# Main.net
KiCad netlist of a schematic drawn in Altium Designer
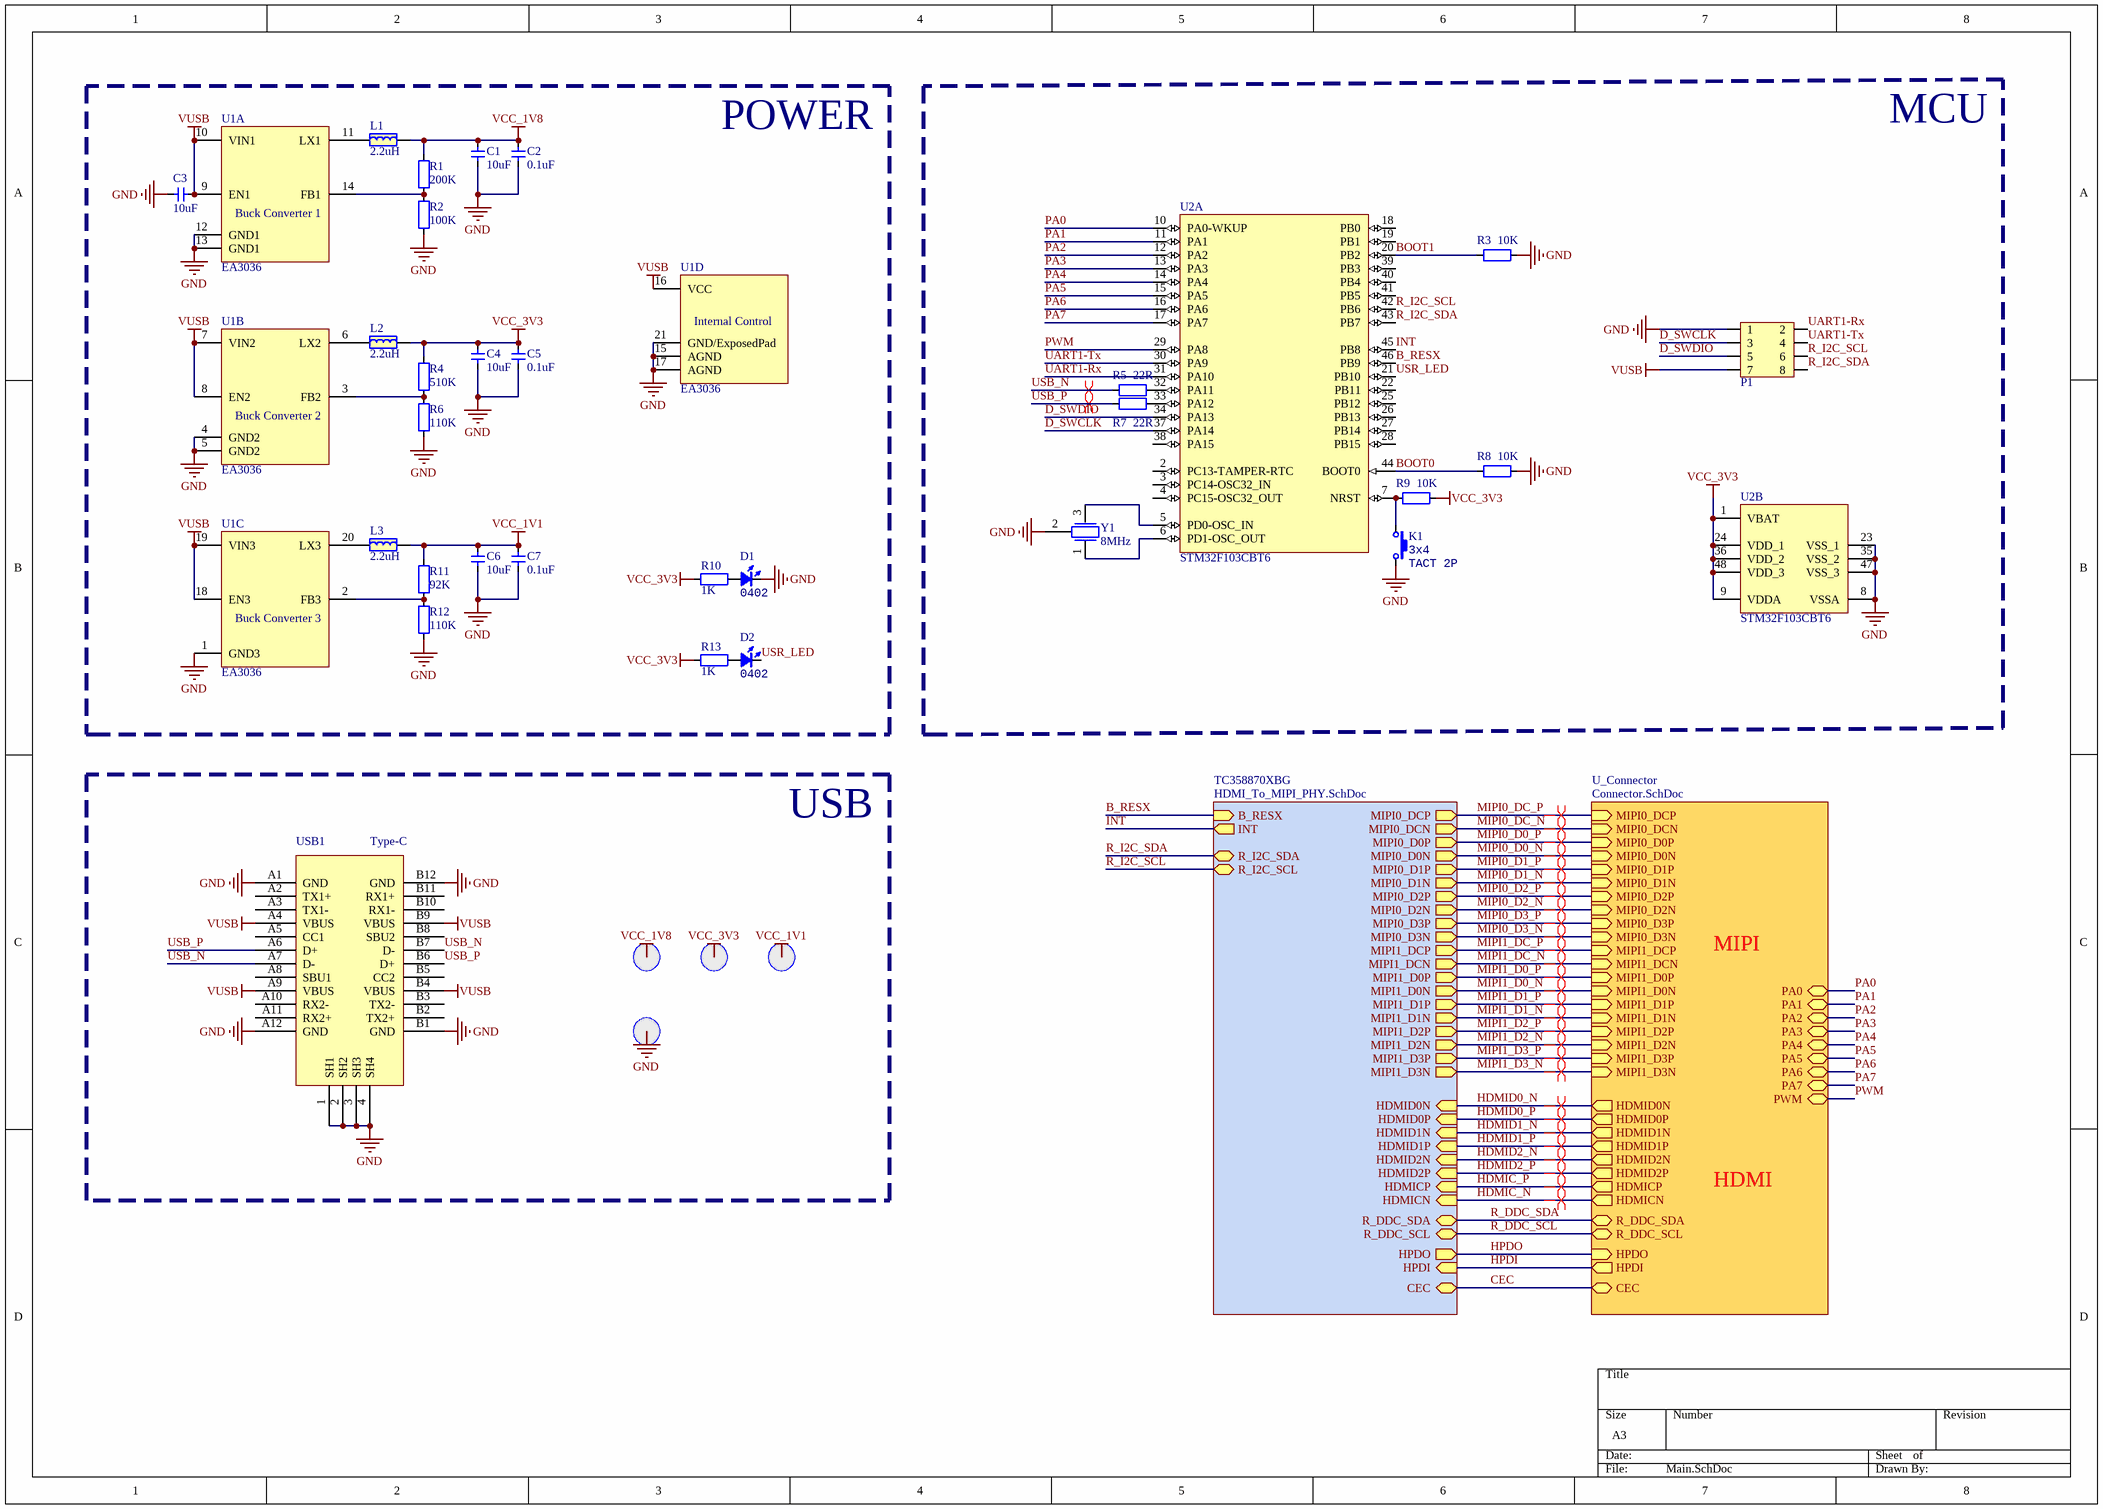
[diagram p0: Main.SchDoc]

(export (version "E")
  (design (tool "Eeschema 10.0.6"))
  (components
    (comp (ref "C1")
      (value "10uF")
      (footprint "CAP_0402")
      (description "Capacitor")
      (libsource (lib "MyPcbLib") (part "电容-0402"))
    )
    (comp (ref "C2")
      (value "0.1uF")
      (footprint "CAP_0402")
      (description "Capacitor")
      (libsource (lib "MyPcbLib") (part "电容-0402"))
    )
    (comp (ref "C3")
      (value "10uF")
      (footprint "CAP_0402")
      (description "Capacitor")
      (libsource (lib "MyPcbLib") (part "电容-0402"))
    )
    (comp (ref "C4")
      (value "10uF")
      (footprint "CAP_0402")
      (description "Capacitor")
      (libsource (lib "MyPcbLib") (part "电容-0402"))
    )
    (comp (ref "C5")
      (value "0.1uF")
      (footprint "CAP_0402")
      (description "Capacitor")
      (libsource (lib "MyPcbLib") (part "电容-0402"))
    )
    (comp (ref "C6")
      (value "10uF")
      (footprint "CAP_0402")
      (description "Capacitor")
      (libsource (lib "MyPcbLib") (part "电容-0402"))
    )
    (comp (ref "C7")
      (value "0.1uF")
      (footprint "CAP_0402")
      (description "Capacitor")
      (libsource (lib "MyPcbLib") (part "电容-0402"))
    )
    (comp (ref "D1")
      (value "color?")
      (footprint "LED_0402_RED")
      (description "LED")
      (fields (field (name "TYPE") "0402"))
      (libsource (lib "KitSprout") (part "LED_0402"))
    )
    (comp (ref "D2")
      (value "color?")
      (footprint "LED_0402_RED")
      (description "LED")
      (fields (field (name "TYPE") "0402"))
      (libsource (lib "KitSprout") (part "LED_0402"))
    )
    (comp (ref "K1")
      (value "3x4")
      (footprint "ButtonTACT_3x4x2_180H")
      (description "Button")
      (fields (field (name "TYPE") "TACT 2P") (field (name "Comment") "TACT 2P"))
      (libsource (lib "KitSprout") (part "ButtonTACT_3x4x2_180"))
    )
    (comp (ref "L1")
      (value "2.2uH")
      (footprint "2520-L")
      (description "磁珠")
      (libsource (lib "MyPcbLib") (part "电感-2520"))
    )
    (comp (ref "L2")
      (value "2.2uH")
      (footprint "2520-L")
      (description "磁珠")
      (libsource (lib "MyPcbLib") (part "电感-2520"))
    )
    (comp (ref "L3")
      (value "2.2uH")
      (footprint "2520-L")
      (description "磁珠")
      (libsource (lib "MyPcbLib") (part "电感-2520"))
    )
    (comp (ref "P1")
      (value "HDR2x4_2.54")
      (footprint "HDR2X4_2.54_180H")
      (description "Header")
      (libsource (lib "MyPcbLib") (part "HDR2x4_2.54"))
    )
    (comp (ref "R1")
      (value "200K")
      (footprint "RES_0402")
      (description "Resistor")
      (libsource (lib "MyPcbLib") (part "电阻-0402"))
    )
    (comp (ref "R2")
      (value "100K")
      (footprint "RES_0402")
      (description "Resistor")
      (libsource (lib "MyPcbLib") (part "电阻-0402"))
    )
    (comp (ref "R3")
      (value "10K")
      (footprint "RES_0402")
      (description "Resistor")
      (libsource (lib "") (part "电阻-0402_1"))
    )
    (comp (ref "R4")
      (value "510K")
      (footprint "RES_0402")
      (description "Resistor")
      (libsource (lib "MyPcbLib") (part "电阻-0402"))
    )
    (comp (ref "R5")
      (value "22R")
      (footprint "RES_0402")
      (description "Resistor")
      (libsource (lib "") (part "电阻-0402_1"))
    )
    (comp (ref "R6")
      (value "110K")
      (footprint "RES_0402")
      (description "Resistor")
      (libsource (lib "MyPcbLib") (part "电阻-0402"))
    )
    (comp (ref "R7")
      (value "22R")
      (footprint "RES_0402")
      (description "Resistor")
      (libsource (lib "") (part "电阻-0402_1"))
    )
    (comp (ref "R8")
      (value "10K")
      (footprint "RES_0402")
      (description "Resistor")
      (libsource (lib "") (part "电阻-0402_1"))
    )
    (comp (ref "R9")
      (value "10K")
      (footprint "RES_0402")
      (description "Resistor")
      (libsource (lib "") (part "电阻-0402_1"))
    )
    (comp (ref "R10")
      (value "1K")
      (footprint "RES_0402")
      (description "Resistor")
      (libsource (lib "") (part "电阻-0402_1"))
    )
    (comp (ref "R11")
      (value "92K")
      (footprint "RES_0402")
      (description "Resistor")
      (libsource (lib "MyPcbLib") (part "电阻-0402"))
    )
    (comp (ref "R12")
      (value "110K")
      (footprint "RES_0402")
      (description "Resistor")
      (libsource (lib "MyPcbLib") (part "电阻-0402"))
    )
    (comp (ref "R13")
      (value "1K")
      (footprint "RES_0402")
      (description "Resistor")
      (libsource (lib "") (part "电阻-0402_1"))
    )
    (comp (ref "T1") (value "测试点") (footprint "TEST_PT") (libsource (lib "MyPcbLib") (part "测试点")))
    (comp (ref "T2") (value "测试点") (footprint "TEST_PT") (libsource (lib "MyPcbLib") (part "测试点")))
    (comp (ref "T3") (value "测试点") (footprint "TEST_PT") (libsource (lib "MyPcbLib") (part "测试点")))
    (comp (ref "T4") (value "测试点") (footprint "TEST_PT") (libsource (lib "MyPcbLib") (part "测试点")))
    (comp (ref "U1") (value "EA3036") (footprint "QFN-20") (libsource (lib "mLib") (part "EA3036")))
    (comp (ref "U2")
      (value "STM32F103CBT6")
      (footprint "LQFP-48")
      (libsource (lib "STMicroelectronics STM32 F1") (part "STM32F103CBT6"))
    )
    (comp (ref "USB1")
      (value "Type-C")
      (footprint "Type-C-TOP")
      (libsource (lib "MyPcbLib") (part "USB-Type-C-TOP"))
    )
    (comp (ref "Y1")
      (value "8MHz")
      (footprint "晶振-3P")
      (description "村田贴片")
      (libsource (lib "MyPcbLib") (part "晶振-3Pin"))
    )
  )
  (nets
    (net (code "1") (name "/BOOT0") (class "Default")
      (node (ref "R8") (pin "1") (pinfunction "1_1") (pintype "passive"))
      (node (ref "U2") (pin "44") (pinfunction "BOOT0_44") (pintype "input"))
    )
    (net (code "2") (name "/BOOT1") (class "Default")
      (node (ref "R3") (pin "1") (pinfunction "1_1") (pintype "passive"))
      (node (ref "U2") (pin "20") (pinfunction "PB2_20") (pintype "bidirectional"))
    )
    (net (code "3") (name "/B_RESX") (class "Default")
      (node (ref "U2") (pin "46") (pinfunction "PB9_46") (pintype "bidirectional"))
    )
    (net (code "5") (name "/D_SWCLK") (class "Default")
      (node (ref "P1") (pin "3") (pinfunction "3_3") (pintype "passive"))
      (node (ref "U2") (pin "37") (pinfunction "PA14_37") (pintype "bidirectional"))
    )
    (net (code "6") (name "/D_SWDIO") (class "Default")
      (node (ref "P1") (pin "5") (pinfunction "5_5") (pintype "passive"))
      (node (ref "U2") (pin "34") (pinfunction "PA13_34") (pintype "bidirectional"))
    )
    (net (code "17") (name "/INT") (class "Default")
      (node (ref "U2") (pin "45") (pinfunction "PB8_45") (pintype "bidirectional"))
    )
    (net (code "38") (name "/PA0") (class "Default")
      (node (ref "U2") (pin "10") (pinfunction "PA0-WKUP_10") (pintype "bidirectional"))
    )
    (net (code "39") (name "/PA1") (class "Default")
      (node (ref "U2") (pin "11") (pinfunction "PA1_11") (pintype "bidirectional"))
    )
    (net (code "40") (name "/PA2") (class "Default")
      (node (ref "U2") (pin "12") (pinfunction "PA2_12") (pintype "bidirectional"))
    )
    (net (code "41") (name "/PA3") (class "Default")
      (node (ref "U2") (pin "13") (pinfunction "PA3_13") (pintype "bidirectional"))
    )
    (net (code "42") (name "/PA4") (class "Default")
      (node (ref "U2") (pin "14") (pinfunction "PA4_14") (pintype "bidirectional"))
    )
    (net (code "43") (name "/PA5") (class "Default")
      (node (ref "U2") (pin "15") (pinfunction "PA5_15") (pintype "bidirectional"))
    )
    (net (code "44") (name "/PA6") (class "Default")
      (node (ref "U2") (pin "16") (pinfunction "PA6_16") (pintype "bidirectional"))
    )
    (net (code "45") (name "/PA7") (class "Default")
      (node (ref "U2") (pin "17") (pinfunction "PA7_17") (pintype "bidirectional"))
    )
    (net (code "46") (name "/PWM") (class "Default")
      (node (ref "U2") (pin "29") (pinfunction "PA8_29") (pintype "bidirectional"))
    )
    (net (code "49") (name "/R_I2C_SCL") (class "Default")
      (node (ref "P1") (pin "6") (pinfunction "6_6") (pintype "passive"))
      (node (ref "U2") (pin "42") (pinfunction "PB6_42") (pintype "bidirectional"))
    )
    (net (code "50") (name "/R_I2C_SDA") (class "Default")
      (node (ref "P1") (pin "8") (pinfunction "8_8") (pintype "passive"))
      (node (ref "U2") (pin "43") (pinfunction "PB7_43") (pintype "bidirectional"))
    )
    (net (code "51") (name "/UART1-Rx") (class "Default")
      (node (ref "P1") (pin "2") (pinfunction "2_2") (pintype "passive"))
      (node (ref "U2") (pin "31") (pinfunction "PA10_31") (pintype "bidirectional"))
    )
    (net (code "52") (name "/UART1-Tx") (class "Default")
      (node (ref "P1") (pin "4") (pinfunction "4_4") (pintype "passive"))
      (node (ref "U2") (pin "30") (pinfunction "PA9_30") (pintype "bidirectional"))
    )
    (net (code "53") (name "/USB_N") (class "Default")
      (node (ref "R5") (pin "1") (pinfunction "1_1") (pintype "passive"))
      (node (ref "USB1") (pin "A7") (pinfunction "D-_A7") (pintype "passive"))
      (node (ref "USB1") (pin "B7") (pinfunction "D-_B7") (pintype "passive"))
    )
    (net (code "54") (name "/USB_P") (class "Default")
      (node (ref "R7") (pin "1") (pinfunction "1_1") (pintype "passive"))
      (node (ref "USB1") (pin "A6") (pinfunction "D+_A6") (pintype "passive"))
      (node (ref "USB1") (pin "B6") (pinfunction "D+_B6") (pintype "passive"))
    )
    (net (code "55") (name "/USR_LED") (class "Default")
      (node (ref "D2") (pin "2") (pinfunction "K_2") (pintype "passive"))
      (node (ref "U2") (pin "21") (pinfunction "PB10_21") (pintype "bidirectional"))
    )
    (net (code "56") (name "GND") (class "Default")
      (node (ref "C1") (pin "1") (pinfunction "1_1") (pintype "passive"))
      (node (ref "C2") (pin "2") (pinfunction "2_2") (pintype "passive"))
      (node (ref "C3") (pin "1") (pinfunction "1_1") (pintype "passive"))
      (node (ref "C4") (pin "1") (pinfunction "1_1") (pintype "passive"))
      (node (ref "C5") (pin "2") (pinfunction "2_2") (pintype "passive"))
      (node (ref "C6") (pin "1") (pinfunction "1_1") (pintype "passive"))
      (node (ref "C7") (pin "2") (pinfunction "2_2") (pintype "passive"))
      (node (ref "D1") (pin "2") (pinfunction "K_2") (pintype "passive"))
      (node (ref "K1") (pin "2") (pinfunction "2_2") (pintype "passive"))
      (node (ref "P1") (pin "1") (pinfunction "1_1") (pintype "passive"))
      (node (ref "R12") (pin "1") (pinfunction "1_1") (pintype "passive"))
      (node (ref "R2") (pin "1") (pinfunction "1_1") (pintype "passive"))
      (node (ref "R3") (pin "2") (pinfunction "2_2") (pintype "passive"))
      (node (ref "R6") (pin "1") (pinfunction "1_1") (pintype "passive"))
      (node (ref "R8") (pin "2") (pinfunction "2_2") (pintype "passive"))
      (node (ref "T4") (pin "0") (pinfunction "0_0") (pintype "passive"))
      (node (ref "U1") (pin "1") (pinfunction "GND3_1") (pintype "power_in"))
      (node (ref "U1") (pin "12") (pinfunction "GND1_12") (pintype "power_in"))
      (node (ref "U1") (pin "13") (pinfunction "GND1_13") (pintype "power_in"))
      (node (ref "U1") (pin "15") (pinfunction "AGND_15") (pintype "power_in"))
      (node (ref "U1") (pin "17") (pinfunction "AGND_17") (pintype "power_in"))
      (node (ref "U1") (pin "21") (pinfunction "GND/ExposedPad_21") (pintype "power_in"))
      (node (ref "U1") (pin "4") (pinfunction "GND2_4") (pintype "power_in"))
      (node (ref "U1") (pin "5") (pinfunction "GND2_5") (pintype "power_in"))
      (node (ref "U2") (pin "23") (pinfunction "VSS_1_23") (pintype "power_in"))
      (node (ref "U2") (pin "35") (pinfunction "VSS_2_35") (pintype "power_in"))
      (node (ref "U2") (pin "47") (pinfunction "VSS_3_47") (pintype "power_in"))
      (node (ref "U2") (pin "8") (pinfunction "VSSA_8") (pintype "power_in"))
      (node (ref "USB1") (pin "1") (pinfunction "SH1_1") (pintype "passive"))
      (node (ref "USB1") (pin "2") (pinfunction "SH2_2") (pintype "passive"))
      (node (ref "USB1") (pin "3") (pinfunction "SH3_3") (pintype "passive"))
      (node (ref "USB1") (pin "4") (pinfunction "SH4_4") (pintype "passive"))
      (node (ref "USB1") (pin "A1") (pinfunction "GND_A1") (pintype "passive"))
      (node (ref "USB1") (pin "A12") (pinfunction "GND_A12") (pintype "passive"))
      (node (ref "USB1") (pin "B1") (pinfunction "GND_B1") (pintype "passive"))
      (node (ref "USB1") (pin "B12") (pinfunction "GND_B12") (pintype "passive"))
      (node (ref "Y1") (pin "2") (pinfunction "2_2") (pintype "passive"))
    )
    (net (code "57") (name "Net-(D1-A)") (class "Default")
      (node (ref "D1") (pin "1") (pinfunction "A_1") (pintype "passive"))
      (node (ref "R10") (pin "2") (pinfunction "2_2") (pintype "passive"))
    )
    (net (code "58") (name "Net-(D2-A)") (class "Default")
      (node (ref "D2") (pin "1") (pinfunction "A_1") (pintype "passive"))
      (node (ref "R13") (pin "2") (pinfunction "2_2") (pintype "passive"))
    )
    (net (code "59") (name "Net-(U1A-FB1)") (class "Default")
      (node (ref "R1") (pin "1") (pinfunction "1_1") (pintype "passive"))
      (node (ref "R2") (pin "2") (pinfunction "2_2") (pintype "passive"))
      (node (ref "U1") (pin "14") (pinfunction "FB1_14") (pintype "passive"))
    )
    (net (code "60") (name "Net-(U1A-LX1)") (class "Default")
      (node (ref "L1") (pin "1") (pintype "passive"))
      (node (ref "U1") (pin "11") (pinfunction "LX1_11") (pintype "passive"))
    )
    (net (code "61") (name "Net-(U1B-FB2)") (class "Default")
      (node (ref "R4") (pin "1") (pinfunction "1_1") (pintype "passive"))
      (node (ref "R6") (pin "2") (pinfunction "2_2") (pintype "passive"))
      (node (ref "U1") (pin "3") (pinfunction "FB2_3") (pintype "passive"))
    )
    (net (code "62") (name "Net-(U1B-LX2)") (class "Default")
      (node (ref "L2") (pin "1") (pintype "passive"))
      (node (ref "U1") (pin "6") (pinfunction "LX2_6") (pintype "passive"))
    )
    (net (code "63") (name "Net-(U1C-FB3)") (class "Default")
      (node (ref "R11") (pin "1") (pinfunction "1_1") (pintype "passive"))
      (node (ref "R12") (pin "2") (pinfunction "2_2") (pintype "passive"))
      (node (ref "U1") (pin "2") (pinfunction "FB3_2") (pintype "passive"))
    )
    (net (code "64") (name "Net-(U1C-LX3)") (class "Default")
      (node (ref "L3") (pin "1") (pintype "passive"))
      (node (ref "U1") (pin "20") (pinfunction "LX3_20") (pintype "passive"))
    )
    (net (code "65") (name "Net-(U2A-NRST)") (class "Default")
      (node (ref "K1") (pin "1") (pinfunction "1_1") (pintype "passive"))
      (node (ref "R9") (pin "1") (pinfunction "1_1") (pintype "passive"))
      (node (ref "U2") (pin "7") (pinfunction "NRST_7") (pintype "bidirectional"))
    )
    (net (code "66") (name "Net-(U2A-PA11)") (class "Default")
      (node (ref "R5") (pin "2") (pinfunction "2_2") (pintype "passive"))
      (node (ref "U2") (pin "32") (pinfunction "PA11_32") (pintype "bidirectional"))
    )
    (net (code "67") (name "Net-(U2A-PA12)") (class "Default")
      (node (ref "R7") (pin "2") (pinfunction "2_2") (pintype "passive"))
      (node (ref "U2") (pin "33") (pinfunction "PA12_33") (pintype "bidirectional"))
    )
    (net (code "68") (name "Net-(U2A-PD0-OSC_IN)") (class "Default")
      (node (ref "U2") (pin "5") (pinfunction "PD0-OSC_IN_5") (pintype "bidirectional"))
      (node (ref "Y1") (pin "3") (pinfunction "3_3") (pintype "passive"))
    )
    (net (code "69") (name "Net-(U2A-PD1-OSC_OUT)") (class "Default")
      (node (ref "U2") (pin "6") (pinfunction "PD1-OSC_OUT_6") (pintype "bidirectional"))
      (node (ref "Y1") (pin "1") (pinfunction "1_1") (pintype "passive"))
    )
    (net (code "70") (name "VCC_1V1") (class "Default")
      (node (ref "C6") (pin "2") (pinfunction "2_2") (pintype "passive"))
      (node (ref "C7") (pin "1") (pinfunction "1_1") (pintype "passive"))
      (node (ref "L3") (pin "2") (pinfunction "2_2") (pintype "passive"))
      (node (ref "R11") (pin "2") (pinfunction "2_2") (pintype "passive"))
      (node (ref "T3") (pin "0") (pinfunction "0_0") (pintype "passive"))
    )
    (net (code "71") (name "VCC_1V8") (class "Default")
      (node (ref "C1") (pin "2") (pinfunction "2_2") (pintype "passive"))
      (node (ref "C2") (pin "1") (pinfunction "1_1") (pintype "passive"))
      (node (ref "L1") (pin "2") (pinfunction "2_2") (pintype "passive"))
      (node (ref "R1") (pin "2") (pinfunction "2_2") (pintype "passive"))
      (node (ref "T1") (pin "0") (pinfunction "0_0") (pintype "passive"))
    )
    (net (code "72") (name "VCC_3V3") (class "Default")
      (node (ref "C4") (pin "2") (pinfunction "2_2") (pintype "passive"))
      (node (ref "C5") (pin "1") (pinfunction "1_1") (pintype "passive"))
      (node (ref "L2") (pin "2") (pinfunction "2_2") (pintype "passive"))
      (node (ref "R10") (pin "1") (pinfunction "1_1") (pintype "passive"))
      (node (ref "R13") (pin "1") (pinfunction "1_1") (pintype "passive"))
      (node (ref "R4") (pin "2") (pinfunction "2_2") (pintype "passive"))
      (node (ref "R9") (pin "2") (pinfunction "2_2") (pintype "passive"))
      (node (ref "T2") (pin "0") (pinfunction "0_0") (pintype "passive"))
      (node (ref "U2") (pin "1") (pinfunction "VBAT_1") (pintype "power_in"))
      (node (ref "U2") (pin "24") (pinfunction "VDD_1_24") (pintype "power_in"))
      (node (ref "U2") (pin "36") (pinfunction "VDD_2_36") (pintype "power_in"))
      (node (ref "U2") (pin "48") (pinfunction "VDD_3_48") (pintype "power_in"))
      (node (ref "U2") (pin "9") (pinfunction "VDDA_9") (pintype "power_in"))
    )
    (net (code "73") (name "VUSB") (class "Default")
      (node (ref "C3") (pin "2") (pinfunction "2_2") (pintype "passive"))
      (node (ref "P1") (pin "7") (pinfunction "7_7") (pintype "passive"))
      (node (ref "U1") (pin "10") (pinfunction "VIN1_10") (pintype "power_in"))
      (node (ref "U1") (pin "16") (pinfunction "VCC_16") (pintype "power_in"))
      (node (ref "U1") (pin "18") (pinfunction "EN3_18") (pintype "passive"))
      (node (ref "U1") (pin "19") (pinfunction "VIN3_19") (pintype "power_in"))
      (node (ref "U1") (pin "7") (pinfunction "VIN2_7") (pintype "power_in"))
      (node (ref "U1") (pin "8") (pinfunction "EN2_8") (pintype "passive"))
      (node (ref "U1") (pin "9") (pinfunction "EN1_9") (pintype "passive"))
      (node (ref "USB1") (pin "A4") (pinfunction "VBUS_A4") (pintype "passive"))
      (node (ref "USB1") (pin "A9") (pinfunction "VBUS_A9") (pintype "passive"))
      (node (ref "USB1") (pin "B4") (pinfunction "VBUS_B4") (pintype "passive"))
      (node (ref "USB1") (pin "B9") (pinfunction "VBUS_B9") (pintype "passive"))
    )
    (net (code "74") (name "unconnected-(U2A-PA15-Pad38)") (class "Default")
      (node (ref "U2") (pin "38") (pinfunction "PA15_38") (pintype "bidirectional"))
    )
    (net (code "75") (name "unconnected-(U2A-PB0-Pad18)") (class "Default")
      (node (ref "U2") (pin "18") (pinfunction "PB0_18") (pintype "bidirectional"))
    )
    (net (code "76") (name "unconnected-(U2A-PB1-Pad19)") (class "Default")
      (node (ref "U2") (pin "19") (pinfunction "PB1_19") (pintype "bidirectional"))
    )
    (net (code "77") (name "unconnected-(U2A-PB3-Pad39)") (class "Default")
      (node (ref "U2") (pin "39") (pinfunction "PB3_39") (pintype "bidirectional"))
    )
    (net (code "78") (name "unconnected-(U2A-PB4-Pad40)") (class "Default")
      (node (ref "U2") (pin "40") (pinfunction "PB4_40") (pintype "bidirectional"))
    )
    (net (code "79") (name "unconnected-(U2A-PB5-Pad41)") (class "Default")
      (node (ref "U2") (pin "41") (pinfunction "PB5_41") (pintype "bidirectional"))
    )
    (net (code "80") (name "unconnected-(U2A-PB11-Pad22)") (class "Default")
      (node (ref "U2") (pin "22") (pinfunction "PB11_22") (pintype "bidirectional"))
    )
    (net (code "81") (name "unconnected-(U2A-PB12-Pad25)") (class "Default")
      (node (ref "U2") (pin "25") (pinfunction "PB12_25") (pintype "bidirectional"))
    )
    (net (code "82") (name "unconnected-(U2A-PB13-Pad26)") (class "Default")
      (node (ref "U2") (pin "26") (pinfunction "PB13_26") (pintype "bidirectional"))
    )
    (net (code "83") (name "unconnected-(U2A-PB14-Pad27)") (class "Default")
      (node (ref "U2") (pin "27") (pinfunction "PB14_27") (pintype "bidirectional"))
    )
    (net (code "84") (name "unconnected-(U2A-PB15-Pad28)") (class "Default")
      (node (ref "U2") (pin "28") (pinfunction "PB15_28") (pintype "bidirectional"))
    )
    (net (code "85") (name "unconnected-(U2A-PC13-TAMPER-RTC-Pad2)") (class "Default")
      (node (ref "U2") (pin "2") (pinfunction "PC13-TAMPER-RTC_2") (pintype "bidirectional"))
    )
    (net (code "86") (name "unconnected-(U2A-PC14-OSC32_IN-Pad3)") (class "Default")
      (node (ref "U2") (pin "3") (pinfunction "PC14-OSC32_IN_3") (pintype "bidirectional"))
    )
    (net (code "87") (name "unconnected-(U2A-PC15-OSC32_OUT-Pad4)") (class "Default")
      (node (ref "U2") (pin "4") (pinfunction "PC15-OSC32_OUT_4") (pintype "bidirectional"))
    )
    (net (code "88") (name "unconnected-(USB1-CC1-PadA5)") (class "Default")
      (node (ref "USB1") (pin "A5") (pinfunction "CC1_A5") (pintype "passive"))
    )
    (net (code "89") (name "unconnected-(USB1-CC2-PadB5)") (class "Default")
      (node (ref "USB1") (pin "B5") (pinfunction "CC2_B5") (pintype "passive"))
    )
    (net (code "90") (name "unconnected-(USB1-RX1+-PadB11)") (class "Default")
      (node (ref "USB1") (pin "B11") (pinfunction "RX1+_B11") (pintype "passive"))
    )
    (net (code "91") (name "unconnected-(USB1-RX1--PadB10)") (class "Default")
      (node (ref "USB1") (pin "B10") (pinfunction "RX1-_B10") (pintype "passive"))
    )
    (net (code "92") (name "unconnected-(USB1-RX2+-PadA11)") (class "Default")
      (node (ref "USB1") (pin "A11") (pinfunction "RX2+_A11") (pintype "passive"))
    )
    (net (code "93") (name "unconnected-(USB1-RX2--PadA10)") (class "Default")
      (node (ref "USB1") (pin "A10") (pinfunction "RX2-_A10") (pintype "passive"))
    )
    (net (code "94") (name "unconnected-(USB1-SBU1-PadA8)") (class "Default")
      (node (ref "USB1") (pin "A8") (pinfunction "SBU1_A8") (pintype "passive"))
    )
    (net (code "95") (name "unconnected-(USB1-SBU2-PadB8)") (class "Default")
      (node (ref "USB1") (pin "B8") (pinfunction "SBU2_B8") (pintype "passive"))
    )
    (net (code "96") (name "unconnected-(USB1-TX1+-PadA2)") (class "Default")
      (node (ref "USB1") (pin "A2") (pinfunction "TX1+_A2") (pintype "passive"))
    )
    (net (code "97") (name "unconnected-(USB1-TX1--PadA3)") (class "Default")
      (node (ref "USB1") (pin "A3") (pinfunction "TX1-_A3") (pintype "passive"))
    )
    (net (code "98") (name "unconnected-(USB1-TX2+-PadB2)") (class "Default")
      (node (ref "USB1") (pin "B2") (pinfunction "TX2+_B2") (pintype "passive"))
    )
    (net (code "99") (name "unconnected-(USB1-TX2--PadB3)") (class "Default")
      (node (ref "USB1") (pin "B3") (pinfunction "TX2-_B3") (pintype "passive"))
    )
  )
)
